# Driver.net
KiCad netlist of a schematic drawn in Altium Designer
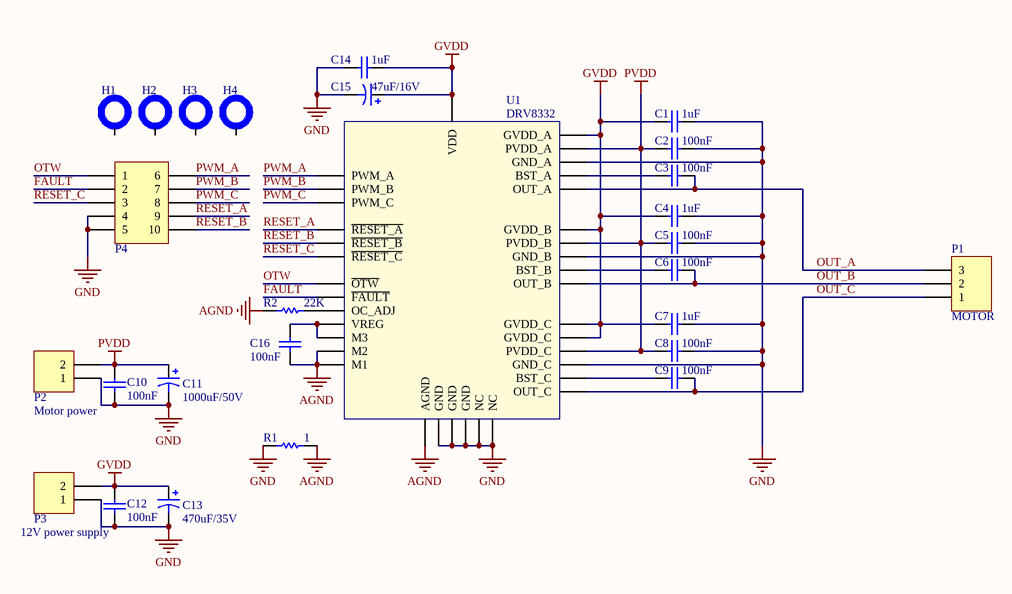
[diagram p0: Driver.SchDoc]

(export (version "E")
  (design (tool "Eeschema 10.0.6"))
  (components
    (comp (ref "C1")
      (value "1uF")
      (footprint "C_0603")
      (description "Capacitor")
      (fields (field (name "Comment") "Cap") (field (name "PUBLISHER") "Altium Limited"))
      (libsource (lib "Miscellaneous Devices") (part "Cap"))
    )
    (comp (ref "C2")
      (value "100nF")
      (footprint "C_0603")
      (description "Capacitor")
      (fields (field (name "Comment") "Cap") (field (name "PUBLISHER") "Altium Limited"))
      (libsource (lib "Miscellaneous Devices") (part "Cap"))
    )
    (comp (ref "C3")
      (value "100nF")
      (footprint "C_0603")
      (description "Capacitor")
      (fields (field (name "Comment") "Cap") (field (name "PUBLISHER") "Altium Limited"))
      (libsource (lib "Miscellaneous Devices") (part "Cap"))
    )
    (comp (ref "C4")
      (value "1uF")
      (footprint "C_0603")
      (description "Capacitor")
      (fields (field (name "Comment") "Cap") (field (name "PUBLISHER") "Altium Limited"))
      (libsource (lib "Miscellaneous Devices") (part "Cap"))
    )
    (comp (ref "C5")
      (value "100nF")
      (footprint "C_0603")
      (description "Capacitor")
      (fields (field (name "Comment") "Cap") (field (name "PUBLISHER") "Altium Limited"))
      (libsource (lib "Miscellaneous Devices") (part "Cap"))
    )
    (comp (ref "C6")
      (value "100nF")
      (footprint "C_0603")
      (description "Capacitor")
      (fields (field (name "Comment") "Cap") (field (name "PUBLISHER") "Altium Limited"))
      (libsource (lib "Miscellaneous Devices") (part "Cap"))
    )
    (comp (ref "C7")
      (value "1uF")
      (footprint "C_0603")
      (description "Capacitor")
      (fields (field (name "Comment") "Cap") (field (name "PUBLISHER") "Altium Limited"))
      (libsource (lib "Miscellaneous Devices") (part "Cap"))
    )
    (comp (ref "C8")
      (value "100nF")
      (footprint "C_0603")
      (description "Capacitor")
      (fields (field (name "Comment") "Cap") (field (name "PUBLISHER") "Altium Limited"))
      (libsource (lib "Miscellaneous Devices") (part "Cap"))
    )
    (comp (ref "C9")
      (value "100nF")
      (footprint "C_0603")
      (description "Capacitor")
      (fields (field (name "Comment") "Cap") (field (name "PUBLISHER") "Altium Limited"))
      (libsource (lib "Miscellaneous Devices") (part "Cap"))
    )
    (comp (ref "C10")
      (value "100nF")
      (footprint "C_0603")
      (description "Capacitor")
      (fields (field (name "Comment") "Cap") (field (name "PUBLISHER") "Altium Limited"))
      (libsource (lib "Miscellaneous Devices") (part "Cap"))
    )
    (comp (ref "C11")
      (value "1000uF/50V")
      (footprint "CP2/6 lying")
      (description "Polarized Capacitor (Radial)")
      (fields (field (name "Comment") "Cap Pol1") (field (name "PUBLISHER") "Altium Limited"))
      (libsource (lib "Miscellaneous Devices") (part "Cap Pol1"))
    )
    (comp (ref "C12")
      (value "100nF")
      (footprint "C_0603")
      (description "Capacitor")
      (fields (field (name "Comment") "Cap") (field (name "PUBLISHER") "Altium Limited"))
      (libsource (lib "Miscellaneous Devices") (part "Cap"))
    )
    (comp (ref "C13")
      (value "470uF/35V")
      (footprint "CAP ALU SIZE G")
      (description "Polarized Capacitor (Radial)")
      (fields (field (name "Comment") "Cap Pol1") (field (name "PUBLISHER") "Altium Limited"))
      (libsource (lib "Miscellaneous Devices") (part "Cap Pol1"))
    )
    (comp (ref "C14")
      (value "1uF")
      (footprint "C_0603")
      (description "Capacitor")
      (fields (field (name "Comment") "Cap") (field (name "PUBLISHER") "Altium Limited"))
      (libsource (lib "Miscellaneous Devices") (part "Cap"))
    )
    (comp (ref "C15")
      (value "47uF/16V")
      (footprint "C_TANTALUM_C")
      (description "Polarized Capacitor (Radial)")
      (fields (field (name "Comment") "Cap Pol1") (field (name "PUBLISHER") "Altium Limited"))
      (libsource (lib "Miscellaneous Devices") (part "Cap Pol1"))
    )
    (comp (ref "C16")
      (value "100nF")
      (footprint "C_0603")
      (description "Capacitor")
      (fields (field (name "Comment") "Cap") (field (name "PUBLISHER") "Altium Limited"))
      (libsource (lib "Miscellaneous Devices") (part "Cap"))
    )
    (comp (ref "H1") (value "3mm hole") (footprint "3mm HOLE") (libsource (lib "My_lib") (part "3mm hole")))
    (comp (ref "H2") (value "3mm hole") (footprint "3mm HOLE") (libsource (lib "My_lib") (part "3mm hole")))
    (comp (ref "H3") (value "3mm hole") (footprint "3mm HOLE") (libsource (lib "My_lib") (part "3mm hole")))
    (comp (ref "H4") (value "3mm hole") (footprint "3mm HOLE") (libsource (lib "My_lib") (part "3mm hole")))
    (comp (ref "P1")
      (value "MOTOR")
      (footprint "DOMINO 3-5mm")
      (description "Header, 3-Pin")
      (fields (field (name "PUBLISHER") "Altium Limited"))
      (libsource (lib "Miscellaneous Connectors") (part "Header 3"))
    )
    (comp (ref "P2")
      (value "Motor power")
      (footprint "DOMINO 2- 5mm")
      (description "Domino, 2-Pin")
      (fields (field (name "PUBLISHER") "Altium Limited"))
      (libsource (lib "PIF_Schematic_Lib") (part "Domino 2"))
    )
    (comp (ref "P3")
      (value "12V power supply")
      (footprint "DOMINO 2- 5mm")
      (description "Domino, 2-Pin")
      (fields (field (name "PUBLISHER") "Altium Limited"))
      (libsource (lib "PIF_Schematic_Lib") (part "Domino 2"))
    )
    (comp (ref "P4")
      (value "Header 5X2")
      (footprint "JP5X2")
      (description "Header, 5-Pin, Dual row")
      (fields (field (name "PUBLISHER") "Altium Limited"))
      (libsource (lib "PIF_Library") (part "Header 5X2"))
    )
    (comp (ref "R1")
      (value "1")
      (footprint "R_0603")
      (description "Resistor")
      (fields (field (name "Comment") "Res1") (field (name "PUBLISHER") "Altium Limited"))
      (libsource (lib "Miscellaneous Devices") (part "Res1"))
    )
    (comp (ref "R2")
      (value "22K")
      (footprint "R_0603")
      (description "Resistor")
      (fields (field (name "Comment") "Res1") (field (name "PUBLISHER") "Altium Limited"))
      (libsource (lib "Miscellaneous Devices") (part "Res1"))
    )
    (comp (ref "U1")
      (value "DRV8332")
      (footprint "HSSOP36_HEATSINK")
      (description "Three-Phase PWM Motor Driver")
      (libsource (lib "My_lib") (part "DRV8332"))
    )
  )
  (nets
    (net (code "1") (name "/FAULT") (class "Default")
      (node (ref "P4") (pin "2") (pinfunction "2_2") (pintype "passive"))
      (node (ref "U1") (pin "3") (pinfunction "~{FAULT}_3") (pintype "passive"))
    )
    (net (code "2") (name "/OTW") (class "Default")
      (node (ref "P4") (pin "1") (pinfunction "1_1") (pintype "passive"))
      (node (ref "U1") (pin "2") (pinfunction "~{OTW}_2") (pintype "passive"))
    )
    (net (code "3") (name "/OUT_A") (class "Default")
      (node (ref "C3") (pin "2") (pinfunction "2_2") (pintype "passive"))
      (node (ref "P1") (pin "3") (pinfunction "3_3") (pintype "passive"))
      (node (ref "U1") (pin "33") (pinfunction "OUT_A_33") (pintype "passive"))
    )
    (net (code "4") (name "/OUT_B") (class "Default")
      (node (ref "C6") (pin "2") (pinfunction "2_2") (pintype "passive"))
      (node (ref "P1") (pin "2") (pinfunction "2_2") (pintype "passive"))
      (node (ref "U1") (pin "30") (pinfunction "OUT_B_30") (pintype "passive"))
    )
    (net (code "5") (name "/OUT_C") (class "Default")
      (node (ref "C9") (pin "2") (pinfunction "2_2") (pintype "passive"))
      (node (ref "P1") (pin "1") (pinfunction "1_1") (pintype "passive"))
      (node (ref "U1") (pin "22") (pinfunction "OUT_C_22") (pintype "passive"))
    )
    (net (code "6") (name "/PWM_A") (class "Default")
      (node (ref "P4") (pin "6") (pinfunction "6_6") (pintype "passive"))
      (node (ref "U1") (pin "4") (pinfunction "PWM_A_4") (pintype "passive"))
    )
    (net (code "7") (name "/PWM_B") (class "Default")
      (node (ref "P4") (pin "7") (pinfunction "7_7") (pintype "passive"))
      (node (ref "U1") (pin "6") (pinfunction "PWM_B_6") (pintype "passive"))
    )
    (net (code "8") (name "/PWM_C") (class "Default")
      (node (ref "P4") (pin "8") (pinfunction "8_8") (pintype "passive"))
      (node (ref "U1") (pin "16") (pinfunction "PWM_C_16") (pintype "passive"))
    )
    (net (code "9") (name "/RESET_A") (class "Default")
      (node (ref "P4") (pin "9") (pinfunction "9_9") (pintype "passive"))
      (node (ref "U1") (pin "5") (pinfunction "~{RESET_A}_5") (pintype "passive"))
    )
    (net (code "10") (name "/RESET_B") (class "Default")
      (node (ref "P4") (pin "10") (pinfunction "10_10") (pintype "passive"))
      (node (ref "U1") (pin "14") (pinfunction "~{RESET_B}_14") (pintype "passive"))
    )
    (net (code "11") (name "/RESET_C") (class "Default")
      (node (ref "P4") (pin "3") (pinfunction "3_3") (pintype "passive"))
      (node (ref "U1") (pin "15") (pinfunction "~{RESET_C}_15") (pintype "passive"))
    )
    (net (code "12") (name "AGND") (class "Default")
      (node (ref "C16") (pin "1") (pinfunction "1_1") (pintype "passive"))
      (node (ref "R1") (pin "2") (pinfunction "2_2") (pintype "passive"))
      (node (ref "R2") (pin "1") (pinfunction "1_1") (pintype "passive"))
      (node (ref "U1") (pin "12") (pinfunction "M2_12") (pintype "passive"))
      (node (ref "U1") (pin "13") (pinfunction "M1_13") (pintype "passive"))
      (node (ref "U1") (pin "9") (pinfunction "AGND_9") (pintype "passive"))
    )
    (net (code "13") (name "GND") (class "Default")
      (node (ref "C1") (pin "2") (pinfunction "2_2") (pintype "passive"))
      (node (ref "C10") (pin "1") (pinfunction "1_1") (pintype "passive"))
      (node (ref "C11") (pin "2") (pinfunction "2_2") (pintype "passive"))
      (node (ref "C12") (pin "1") (pinfunction "1_1") (pintype "passive"))
      (node (ref "C13") (pin "2") (pinfunction "2_2") (pintype "passive"))
      (node (ref "C14") (pin "1") (pinfunction "1_1") (pintype "passive"))
      (node (ref "C15") (pin "2") (pinfunction "2_2") (pintype "passive"))
      (node (ref "C2") (pin "2") (pinfunction "2_2") (pintype "passive"))
      (node (ref "C4") (pin "2") (pinfunction "2_2") (pintype "passive"))
      (node (ref "C5") (pin "2") (pinfunction "2_2") (pintype "passive"))
      (node (ref "C7") (pin "2") (pinfunction "2_2") (pintype "passive"))
      (node (ref "C8") (pin "2") (pinfunction "2_2") (pintype "passive"))
      (node (ref "P2") (pin "1") (pinfunction "1_1") (pintype "passive"))
      (node (ref "P3") (pin "1") (pinfunction "1_1") (pintype "passive"))
      (node (ref "P4") (pin "4") (pinfunction "4_4") (pintype "passive"))
      (node (ref "P4") (pin "5") (pinfunction "5_5") (pintype "passive"))
      (node (ref "R1") (pin "1") (pinfunction "1_1") (pintype "passive"))
      (node (ref "U1") (pin "23") (pinfunction "GND_C_23") (pintype "passive"))
      (node (ref "U1") (pin "24") (pinfunction "GND_24") (pintype "passive"))
      (node (ref "U1") (pin "25") (pinfunction "GND_25") (pintype "passive"))
      (node (ref "U1") (pin "26") (pinfunction "NC_26") (pintype "passive"))
      (node (ref "U1") (pin "27") (pinfunction "NC_27") (pintype "passive"))
      (node (ref "U1") (pin "31") (pinfunction "GND_B_31") (pintype "passive"))
      (node (ref "U1") (pin "32") (pinfunction "GND_A_32") (pintype "passive"))
      (node (ref "U1") (pin "8") (pinfunction "GND_8") (pintype "passive"))
    )
    (net (code "14") (name "GVDD") (class "Default")
      (node (ref "C1") (pin "1") (pinfunction "1_1") (pintype "passive"))
      (node (ref "C12") (pin "2") (pinfunction "2_2") (pintype "passive"))
      (node (ref "C13") (pin "1") (pinfunction "1_1") (pintype "passive"))
      (node (ref "C14") (pin "2") (pinfunction "2_2") (pintype "passive"))
      (node (ref "C15") (pin "1") (pinfunction "1_1") (pintype "passive"))
      (node (ref "C4") (pin "1") (pinfunction "1_1") (pintype "passive"))
      (node (ref "C7") (pin "1") (pinfunction "1_1") (pintype "passive"))
      (node (ref "P3") (pin "2") (pinfunction "2_2") (pintype "passive"))
      (node (ref "U1") (pin "1") (pinfunction "GVDD_B_1") (pintype "passive"))
      (node (ref "U1") (pin "17") (pinfunction "VDD_17") (pintype "passive"))
      (node (ref "U1") (pin "18") (pinfunction "GVDD_C_18") (pintype "passive"))
      (node (ref "U1") (pin "19") (pinfunction "GVDD_C_19") (pintype "passive"))
      (node (ref "U1") (pin "36") (pinfunction "GVDD_A_36") (pintype "passive"))
    )
    (net (code "15") (name "Net-(U1-BST_A)") (class "Default")
      (node (ref "C3") (pin "1") (pinfunction "1_1") (pintype "passive"))
      (node (ref "U1") (pin "35") (pinfunction "BST_A_35") (pintype "passive"))
    )
    (net (code "16") (name "Net-(U1-BST_B)") (class "Default")
      (node (ref "C6") (pin "1") (pinfunction "1_1") (pintype "passive"))
      (node (ref "U1") (pin "28") (pinfunction "BST_B_28") (pintype "passive"))
    )
    (net (code "17") (name "Net-(U1-BST_C)") (class "Default")
      (node (ref "C9") (pin "1") (pinfunction "1_1") (pintype "passive"))
      (node (ref "U1") (pin "20") (pinfunction "BST_C_20") (pintype "passive"))
    )
    (net (code "18") (name "Net-(U1-M3)") (class "Default")
      (node (ref "C16") (pin "2") (pinfunction "2_2") (pintype "passive"))
      (node (ref "U1") (pin "10") (pinfunction "VREG_10") (pintype "passive"))
      (node (ref "U1") (pin "11") (pinfunction "M3_11") (pintype "passive"))
    )
    (net (code "19") (name "Net-(U1-OC_ADJ)") (class "Default")
      (node (ref "R2") (pin "2") (pinfunction "2_2") (pintype "passive"))
      (node (ref "U1") (pin "7") (pinfunction "OC_ADJ_7") (pintype "passive"))
    )
    (net (code "20") (name "PVDD") (class "Default")
      (node (ref "C10") (pin "2") (pinfunction "2_2") (pintype "passive"))
      (node (ref "C11") (pin "1") (pinfunction "1_1") (pintype "passive"))
      (node (ref "C2") (pin "1") (pinfunction "1_1") (pintype "passive"))
      (node (ref "C5") (pin "1") (pinfunction "1_1") (pintype "passive"))
      (node (ref "C8") (pin "1") (pinfunction "1_1") (pintype "passive"))
      (node (ref "P2") (pin "2") (pinfunction "2_2") (pintype "passive"))
      (node (ref "U1") (pin "21") (pinfunction "PVDD_C_21") (pintype "passive"))
      (node (ref "U1") (pin "29") (pinfunction "PVDD_B_29") (pintype "passive"))
      (node (ref "U1") (pin "34") (pinfunction "PVDD_A_34") (pintype "passive"))
    )
    (net (code "21") (name "unconnected-(H1-GND-Pad0)") (class "Default")
      (node (ref "H1") (pin "0") (pinfunction "GND_0") (pintype "passive"))
    )
    (net (code "22") (name "unconnected-(H2-GND-Pad0)") (class "Default")
      (node (ref "H2") (pin "0") (pinfunction "GND_0") (pintype "passive"))
    )
    (net (code "23") (name "unconnected-(H3-GND-Pad0)") (class "Default")
      (node (ref "H3") (pin "0") (pinfunction "GND_0") (pintype "passive"))
    )
    (net (code "24") (name "unconnected-(H4-GND-Pad0)") (class "Default")
      (node (ref "H4") (pin "0") (pinfunction "GND_0") (pintype "passive"))
    )
  )
)
